# Main.net
KiCad netlist of a schematic drawn in Altium Designer
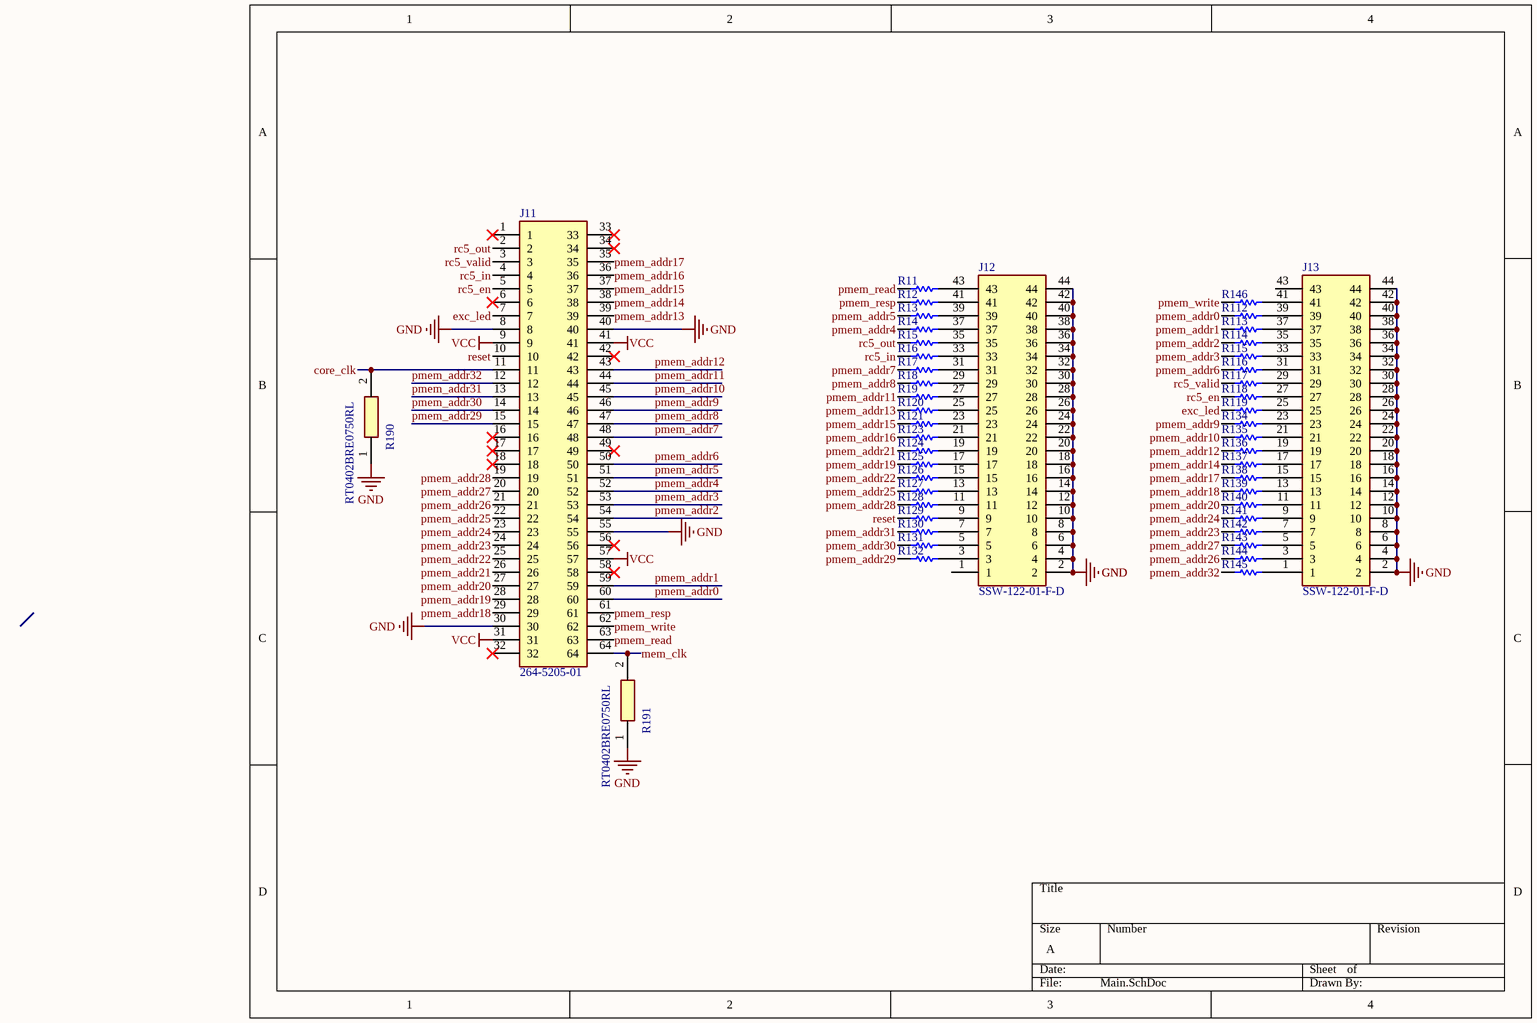
[diagram p0: Main.SchDoc]

(export (version "E")
  (design (tool "Eeschema 10.0.6"))
  (components
    (comp (ref "J11")
      (value "264-5205-01")
      (footprint "SamacSys:264-5205-01_1")
      (description "Connector")
      (fields (field (name "MOUSER PART NUMBER") "517-264-5205-01"))
      (libsource (lib "*") (part "264-5205-01"))
    )
    (comp (ref "J12")
      (value "SSW-122-01-F-D")
      (footprint "SamacSys:SSW-122-XX-YYY-D")
      (description "Connector")
      (fields (field (name "MOUSER PART NUMBER") "200-SSW12201FD"))
      (libsource (lib "SamacSys") (part "SSW-122-01-F-D"))
    )
    (comp (ref "J13")
      (value "SSW-122-01-F-D")
      (footprint "SamacSys:SSW-122-XX-YYY-D")
      (description "Connector")
      (fields (field (name "MOUSER PART NUMBER") "200-SSW12201FD"))
      (libsource (lib "SamacSys") (part "SSW-122-01-F-D"))
    )
    (comp (ref "R11")
      (value "ERJ-U020R00X")
      (footprint "RESC1005X40X25NL05T10")
      (fields (field (name "MANUFACTURER") "Panasonic"))
      (libsource (lib "Altium Content Vault") (part "RES"))
    )
    (comp (ref "R12")
      (value "ERJ-U020R00X")
      (footprint "RESC1005X40X25NL05T10")
      (fields (field (name "MANUFACTURER") "Panasonic"))
      (libsource (lib "Altium Content Vault") (part "RES"))
    )
    (comp (ref "R13")
      (value "ERJ-U020R00X")
      (footprint "RESC1005X40X25NL05T10")
      (fields (field (name "MANUFACTURER") "Panasonic"))
      (libsource (lib "Altium Content Vault") (part "RES"))
    )
    (comp (ref "R14")
      (value "ERJ-U020R00X")
      (footprint "RESC1005X40X25NL05T10")
      (fields (field (name "MANUFACTURER") "Panasonic"))
      (libsource (lib "Altium Content Vault") (part "RES"))
    )
    (comp (ref "R15")
      (value "ERJ-U020R00X")
      (footprint "RESC1005X40X25NL05T10")
      (fields (field (name "MANUFACTURER") "Panasonic"))
      (libsource (lib "Altium Content Vault") (part "RES"))
    )
    (comp (ref "R16")
      (value "ERJ-U020R00X")
      (footprint "RESC1005X40X25NL05T10")
      (fields (field (name "MANUFACTURER") "Panasonic"))
      (libsource (lib "Altium Content Vault") (part "RES"))
    )
    (comp (ref "R17")
      (value "ERJ-U020R00X")
      (footprint "RESC1005X40X25NL05T10")
      (fields (field (name "MANUFACTURER") "Panasonic"))
      (libsource (lib "Altium Content Vault") (part "RES"))
    )
    (comp (ref "R18")
      (value "ERJ-U020R00X")
      (footprint "RESC1005X40X25NL05T10")
      (fields (field (name "MANUFACTURER") "Panasonic"))
      (libsource (lib "Altium Content Vault") (part "RES"))
    )
    (comp (ref "R19")
      (value "ERJ-U020R00X")
      (footprint "RESC1005X40X25NL05T10")
      (fields (field (name "MANUFACTURER") "Panasonic"))
      (libsource (lib "Altium Content Vault") (part "RES"))
    )
    (comp (ref "R112")
      (value "ERJ-U020R00X")
      (footprint "RESC1005X40X25NL05T10")
      (fields (field (name "MANUFACTURER") "Panasonic"))
      (libsource (lib "Altium Content Vault") (part "RES"))
    )
    (comp (ref "R113")
      (value "ERJ-U020R00X")
      (footprint "RESC1005X40X25NL05T10")
      (fields (field (name "MANUFACTURER") "Panasonic"))
      (libsource (lib "Altium Content Vault") (part "RES"))
    )
    (comp (ref "R114")
      (value "ERJ-U020R00X")
      (footprint "RESC1005X40X25NL05T10")
      (fields (field (name "MANUFACTURER") "Panasonic"))
      (libsource (lib "Altium Content Vault") (part "RES"))
    )
    (comp (ref "R115")
      (value "ERJ-U020R00X")
      (footprint "RESC1005X40X25NL05T10")
      (fields (field (name "MANUFACTURER") "Panasonic"))
      (libsource (lib "Altium Content Vault") (part "RES"))
    )
    (comp (ref "R116")
      (value "ERJ-U020R00X")
      (footprint "RESC1005X40X25NL05T10")
      (fields (field (name "MANUFACTURER") "Panasonic"))
      (libsource (lib "Altium Content Vault") (part "RES"))
    )
    (comp (ref "R117")
      (value "ERJ-U020R00X")
      (footprint "RESC1005X40X25NL05T10")
      (fields (field (name "MANUFACTURER") "Panasonic"))
      (libsource (lib "Altium Content Vault") (part "RES"))
    )
    (comp (ref "R118")
      (value "ERJ-U020R00X")
      (footprint "RESC1005X40X25NL05T10")
      (fields (field (name "MANUFACTURER") "Panasonic"))
      (libsource (lib "Altium Content Vault") (part "RES"))
    )
    (comp (ref "R119")
      (value "ERJ-U020R00X")
      (footprint "RESC1005X40X25NL05T10")
      (fields (field (name "MANUFACTURER") "Panasonic"))
      (libsource (lib "Altium Content Vault") (part "RES"))
    )
    (comp (ref "R120")
      (value "ERJ-U020R00X")
      (footprint "RESC1005X40X25NL05T10")
      (fields (field (name "MANUFACTURER") "Panasonic"))
      (libsource (lib "Altium Content Vault") (part "RES"))
    )
    (comp (ref "R121")
      (value "ERJ-U020R00X")
      (footprint "RESC1005X40X25NL05T10")
      (fields (field (name "MANUFACTURER") "Panasonic"))
      (libsource (lib "Altium Content Vault") (part "RES"))
    )
    (comp (ref "R123")
      (value "ERJ-U020R00X")
      (footprint "RESC1005X40X25NL05T10")
      (fields (field (name "MANUFACTURER") "Panasonic"))
      (libsource (lib "Altium Content Vault") (part "RES"))
    )
    (comp (ref "R124")
      (value "ERJ-U020R00X")
      (footprint "RESC1005X40X25NL05T10")
      (fields (field (name "MANUFACTURER") "Panasonic"))
      (libsource (lib "Altium Content Vault") (part "RES"))
    )
    (comp (ref "R125")
      (value "ERJ-U020R00X")
      (footprint "RESC1005X40X25NL05T10")
      (fields (field (name "MANUFACTURER") "Panasonic"))
      (libsource (lib "Altium Content Vault") (part "RES"))
    )
    (comp (ref "R126")
      (value "ERJ-U020R00X")
      (footprint "RESC1005X40X25NL05T10")
      (fields (field (name "MANUFACTURER") "Panasonic"))
      (libsource (lib "Altium Content Vault") (part "RES"))
    )
    (comp (ref "R127")
      (value "ERJ-U020R00X")
      (footprint "RESC1005X40X25NL05T10")
      (fields (field (name "MANUFACTURER") "Panasonic"))
      (libsource (lib "Altium Content Vault") (part "RES"))
    )
    (comp (ref "R128")
      (value "ERJ-U020R00X")
      (footprint "RESC1005X40X25NL05T10")
      (fields (field (name "MANUFACTURER") "Panasonic"))
      (libsource (lib "Altium Content Vault") (part "RES"))
    )
    (comp (ref "R129")
      (value "ERJ-U020R00X")
      (footprint "RESC1005X40X25NL05T10")
      (fields (field (name "MANUFACTURER") "Panasonic"))
      (libsource (lib "Altium Content Vault") (part "RES"))
    )
    (comp (ref "R130")
      (value "ERJ-U020R00X")
      (footprint "RESC1005X40X25NL05T10")
      (fields (field (name "MANUFACTURER") "Panasonic"))
      (libsource (lib "Altium Content Vault") (part "RES"))
    )
    (comp (ref "R131")
      (value "ERJ-U020R00X")
      (footprint "RESC1005X40X25NL05T10")
      (fields (field (name "MANUFACTURER") "Panasonic"))
      (libsource (lib "Altium Content Vault") (part "RES"))
    )
    (comp (ref "R132")
      (value "ERJ-U020R00X")
      (footprint "RESC1005X40X25NL05T10")
      (fields (field (name "MANUFACTURER") "Panasonic"))
      (libsource (lib "Altium Content Vault") (part "RES"))
    )
    (comp (ref "R134")
      (value "ERJ-U020R00X")
      (footprint "RESC1005X40X25NL05T10")
      (fields (field (name "MANUFACTURER") "Panasonic"))
      (libsource (lib "Altium Content Vault") (part "RES"))
    )
    (comp (ref "R135")
      (value "ERJ-U020R00X")
      (footprint "RESC1005X40X25NL05T10")
      (fields (field (name "MANUFACTURER") "Panasonic"))
      (libsource (lib "Altium Content Vault") (part "RES"))
    )
    (comp (ref "R136")
      (value "ERJ-U020R00X")
      (footprint "RESC1005X40X25NL05T10")
      (fields (field (name "MANUFACTURER") "Panasonic"))
      (libsource (lib "Altium Content Vault") (part "RES"))
    )
    (comp (ref "R137")
      (value "ERJ-U020R00X")
      (footprint "RESC1005X40X25NL05T10")
      (fields (field (name "MANUFACTURER") "Panasonic"))
      (libsource (lib "Altium Content Vault") (part "RES"))
    )
    (comp (ref "R138")
      (value "ERJ-U020R00X")
      (footprint "RESC1005X40X25NL05T10")
      (fields (field (name "MANUFACTURER") "Panasonic"))
      (libsource (lib "Altium Content Vault") (part "RES"))
    )
    (comp (ref "R139")
      (value "ERJ-U020R00X")
      (footprint "RESC1005X40X25NL05T10")
      (fields (field (name "MANUFACTURER") "Panasonic"))
      (libsource (lib "Altium Content Vault") (part "RES"))
    )
    (comp (ref "R140")
      (value "ERJ-U020R00X")
      (footprint "RESC1005X40X25NL05T10")
      (fields (field (name "MANUFACTURER") "Panasonic"))
      (libsource (lib "Altium Content Vault") (part "RES"))
    )
    (comp (ref "R141")
      (value "ERJ-U020R00X")
      (footprint "RESC1005X40X25NL05T10")
      (fields (field (name "MANUFACTURER") "Panasonic"))
      (libsource (lib "Altium Content Vault") (part "RES"))
    )
    (comp (ref "R142")
      (value "ERJ-U020R00X")
      (footprint "RESC1005X40X25NL05T10")
      (fields (field (name "MANUFACTURER") "Panasonic"))
      (libsource (lib "Altium Content Vault") (part "RES"))
    )
    (comp (ref "R143")
      (value "ERJ-U020R00X")
      (footprint "RESC1005X40X25NL05T10")
      (fields (field (name "MANUFACTURER") "Panasonic"))
      (libsource (lib "Altium Content Vault") (part "RES"))
    )
    (comp (ref "R144")
      (value "ERJ-U020R00X")
      (footprint "RESC1005X40X25NL05T10")
      (fields (field (name "MANUFACTURER") "Panasonic"))
      (libsource (lib "Altium Content Vault") (part "RES"))
    )
    (comp (ref "R145")
      (value "ERJ-U020R00X")
      (footprint "RESC1005X40X25NL05T10")
      (fields (field (name "MANUFACTURER") "Panasonic"))
      (libsource (lib "Altium Content Vault") (part "RES"))
    )
    (comp (ref "R146")
      (value "ERJ-U020R00X")
      (footprint "RESC1005X40X25NL05T10")
      (fields (field (name "MANUFACTURER") "Panasonic"))
      (libsource (lib "Altium Content Vault") (part "RES"))
    )
    (comp (ref "R190")
      (value "RT0402BRE0750RL")
      (footprint "SamacSys:RESC1005X35N")
      (description "Resistor")
      (fields (field (name "MOUSER PART NUMBER") "603-RT0402BRE0750RL"))
      (libsource (lib "*") (part "RT0402BRE0750RL"))
    )
    (comp (ref "R191")
      (value "RT0402BRE0750RL")
      (footprint "SamacSys:RESC1005X35N")
      (description "Resistor")
      (fields (field (name "MOUSER PART NUMBER") "603-RT0402BRE0750RL"))
      (libsource (lib "*") (part "RT0402BRE0750RL"))
    )
  )
  (nets
    (net (code "1") (name "/core_clk") (class "Default")
      (node (ref "J11") (pin "11") (pinfunction "11_11") (pintype "passive"))
      (node (ref "R190") (pin "2") (pinfunction "2_2") (pintype "passive"))
    )
    (net (code "2") (name "/exc_led") (class "Default")
      (node (ref "J11") (pin "7") (pinfunction "7_7") (pintype "passive"))
      (node (ref "R119") (pin "1") (pinfunction "1_1") (pintype "passive"))
    )
    (net (code "3") (name "/mem_clk") (class "Default")
      (node (ref "J11") (pin "64") (pinfunction "64_64") (pintype "passive"))
      (node (ref "R191") (pin "2") (pinfunction "2_2") (pintype "passive"))
    )
    (net (code "4") (name "/pmem_addr0") (class "Default")
      (node (ref "J11") (pin "60") (pinfunction "60_60") (pintype "passive"))
      (node (ref "R112") (pin "1") (pinfunction "1_1") (pintype "passive"))
    )
    (net (code "5") (name "/pmem_addr1") (class "Default")
      (node (ref "J11") (pin "59") (pinfunction "59_59") (pintype "passive"))
      (node (ref "R113") (pin "1") (pinfunction "1_1") (pintype "passive"))
    )
    (net (code "6") (name "/pmem_addr2") (class "Default")
      (node (ref "J11") (pin "54") (pinfunction "54_54") (pintype "passive"))
      (node (ref "R114") (pin "1") (pinfunction "1_1") (pintype "passive"))
    )
    (net (code "7") (name "/pmem_addr3") (class "Default")
      (node (ref "J11") (pin "53") (pinfunction "53_53") (pintype "passive"))
      (node (ref "R115") (pin "1") (pinfunction "1_1") (pintype "passive"))
    )
    (net (code "8") (name "/pmem_addr4") (class "Default")
      (node (ref "J11") (pin "52") (pinfunction "52_52") (pintype "passive"))
      (node (ref "R14") (pin "1") (pinfunction "1_1") (pintype "passive"))
    )
    (net (code "9") (name "/pmem_addr5") (class "Default")
      (node (ref "J11") (pin "51") (pinfunction "51_51") (pintype "passive"))
      (node (ref "R13") (pin "1") (pinfunction "1_1") (pintype "passive"))
    )
    (net (code "10") (name "/pmem_addr6") (class "Default")
      (node (ref "J11") (pin "50") (pinfunction "50_50") (pintype "passive"))
      (node (ref "R116") (pin "1") (pinfunction "1_1") (pintype "passive"))
    )
    (net (code "11") (name "/pmem_addr7") (class "Default")
      (node (ref "J11") (pin "48") (pinfunction "48_48") (pintype "passive"))
      (node (ref "R17") (pin "1") (pinfunction "1_1") (pintype "passive"))
    )
    (net (code "12") (name "/pmem_addr8") (class "Default")
      (node (ref "J11") (pin "47") (pinfunction "47_47") (pintype "passive"))
      (node (ref "R18") (pin "1") (pinfunction "1_1") (pintype "passive"))
    )
    (net (code "13") (name "/pmem_addr9") (class "Default")
      (node (ref "J11") (pin "46") (pinfunction "46_46") (pintype "passive"))
      (node (ref "R134") (pin "1") (pinfunction "1_1") (pintype "passive"))
    )
    (net (code "14") (name "/pmem_addr10") (class "Default")
      (node (ref "J11") (pin "45") (pinfunction "45_45") (pintype "passive"))
      (node (ref "R135") (pin "1") (pinfunction "1_1") (pintype "passive"))
    )
    (net (code "15") (name "/pmem_addr11") (class "Default")
      (node (ref "J11") (pin "44") (pinfunction "44_44") (pintype "passive"))
      (node (ref "R19") (pin "1") (pinfunction "1_1") (pintype "passive"))
    )
    (net (code "16") (name "/pmem_addr12") (class "Default")
      (node (ref "J11") (pin "43") (pinfunction "43_43") (pintype "passive"))
      (node (ref "R136") (pin "1") (pinfunction "1_1") (pintype "passive"))
    )
    (net (code "17") (name "/pmem_addr13") (class "Default")
      (node (ref "J11") (pin "39") (pinfunction "39_39") (pintype "passive"))
      (node (ref "R120") (pin "1") (pinfunction "1_1") (pintype "passive"))
    )
    (net (code "18") (name "/pmem_addr14") (class "Default")
      (node (ref "J11") (pin "38") (pinfunction "38_38") (pintype "passive"))
      (node (ref "R137") (pin "1") (pinfunction "1_1") (pintype "passive"))
    )
    (net (code "19") (name "/pmem_addr15") (class "Default")
      (node (ref "J11") (pin "37") (pinfunction "37_37") (pintype "passive"))
      (node (ref "R121") (pin "1") (pinfunction "1_1") (pintype "passive"))
    )
    (net (code "20") (name "/pmem_addr16") (class "Default")
      (node (ref "J11") (pin "36") (pinfunction "36_36") (pintype "passive"))
      (node (ref "R123") (pin "1") (pinfunction "1_1") (pintype "passive"))
    )
    (net (code "21") (name "/pmem_addr17") (class "Default")
      (node (ref "J11") (pin "35") (pinfunction "35_35") (pintype "passive"))
      (node (ref "R138") (pin "1") (pinfunction "1_1") (pintype "passive"))
    )
    (net (code "22") (name "/pmem_addr18") (class "Default")
      (node (ref "J11") (pin "29") (pinfunction "29_29") (pintype "passive"))
      (node (ref "R139") (pin "1") (pinfunction "1_1") (pintype "passive"))
    )
    (net (code "23") (name "/pmem_addr19") (class "Default")
      (node (ref "J11") (pin "28") (pinfunction "28_28") (pintype "passive"))
      (node (ref "R125") (pin "1") (pinfunction "1_1") (pintype "passive"))
    )
    (net (code "24") (name "/pmem_addr20") (class "Default")
      (node (ref "J11") (pin "27") (pinfunction "27_27") (pintype "passive"))
      (node (ref "R140") (pin "1") (pinfunction "1_1") (pintype "passive"))
    )
    (net (code "25") (name "/pmem_addr21") (class "Default")
      (node (ref "J11") (pin "26") (pinfunction "26_26") (pintype "passive"))
      (node (ref "R124") (pin "1") (pinfunction "1_1") (pintype "passive"))
    )
    (net (code "26") (name "/pmem_addr22") (class "Default")
      (node (ref "J11") (pin "25") (pinfunction "25_25") (pintype "passive"))
      (node (ref "R126") (pin "1") (pinfunction "1_1") (pintype "passive"))
    )
    (net (code "27") (name "/pmem_addr23") (class "Default")
      (node (ref "J11") (pin "24") (pinfunction "24_24") (pintype "passive"))
      (node (ref "R142") (pin "1") (pinfunction "1_1") (pintype "passive"))
    )
    (net (code "28") (name "/pmem_addr24") (class "Default")
      (node (ref "J11") (pin "23") (pinfunction "23_23") (pintype "passive"))
      (node (ref "R141") (pin "1") (pinfunction "1_1") (pintype "passive"))
    )
    (net (code "29") (name "/pmem_addr25") (class "Default")
      (node (ref "J11") (pin "22") (pinfunction "22_22") (pintype "passive"))
      (node (ref "R127") (pin "1") (pinfunction "1_1") (pintype "passive"))
    )
    (net (code "30") (name "/pmem_addr26") (class "Default")
      (node (ref "J11") (pin "21") (pinfunction "21_21") (pintype "passive"))
      (node (ref "R144") (pin "1") (pinfunction "1_1") (pintype "passive"))
    )
    (net (code "31") (name "/pmem_addr27") (class "Default")
      (node (ref "J11") (pin "20") (pinfunction "20_20") (pintype "passive"))
      (node (ref "R143") (pin "1") (pinfunction "1_1") (pintype "passive"))
    )
    (net (code "32") (name "/pmem_addr28") (class "Default")
      (node (ref "J11") (pin "19") (pinfunction "19_19") (pintype "passive"))
      (node (ref "R128") (pin "1") (pinfunction "1_1") (pintype "passive"))
    )
    (net (code "33") (name "/pmem_addr29") (class "Default")
      (node (ref "J11") (pin "15") (pinfunction "15_15") (pintype "passive"))
      (node (ref "R132") (pin "1") (pinfunction "1_1") (pintype "passive"))
    )
    (net (code "34") (name "/pmem_addr30") (class "Default")
      (node (ref "J11") (pin "14") (pinfunction "14_14") (pintype "passive"))
      (node (ref "R131") (pin "1") (pinfunction "1_1") (pintype "passive"))
    )
    (net (code "35") (name "/pmem_addr31") (class "Default")
      (node (ref "J11") (pin "13") (pinfunction "13_13") (pintype "passive"))
      (node (ref "R130") (pin "1") (pinfunction "1_1") (pintype "passive"))
    )
    (net (code "36") (name "/pmem_addr32") (class "Default")
      (node (ref "J11") (pin "12") (pinfunction "12_12") (pintype "passive"))
      (node (ref "R145") (pin "1") (pinfunction "1_1") (pintype "passive"))
    )
    (net (code "37") (name "/pmem_read") (class "Default")
      (node (ref "J11") (pin "63") (pinfunction "63_63") (pintype "passive"))
      (node (ref "R11") (pin "1") (pinfunction "1_1") (pintype "passive"))
    )
    (net (code "38") (name "/pmem_resp") (class "Default")
      (node (ref "J11") (pin "61") (pinfunction "61_61") (pintype "passive"))
      (node (ref "R12") (pin "1") (pinfunction "1_1") (pintype "passive"))
    )
    (net (code "39") (name "/pmem_write") (class "Default")
      (node (ref "J11") (pin "62") (pinfunction "62_62") (pintype "passive"))
      (node (ref "R146") (pin "1") (pinfunction "1_1") (pintype "passive"))
    )
    (net (code "40") (name "/rc5_en") (class "Default")
      (node (ref "J11") (pin "5") (pinfunction "5_5") (pintype "passive"))
      (node (ref "R118") (pin "1") (pinfunction "1_1") (pintype "passive"))
    )
    (net (code "41") (name "/rc5_in") (class "Default")
      (node (ref "J11") (pin "4") (pinfunction "4_4") (pintype "passive"))
      (node (ref "R16") (pin "1") (pinfunction "1_1") (pintype "passive"))
    )
    (net (code "42") (name "/rc5_out") (class "Default")
      (node (ref "J11") (pin "2") (pinfunction "2_2") (pintype "passive"))
      (node (ref "R15") (pin "1") (pinfunction "1_1") (pintype "passive"))
    )
    (net (code "43") (name "/rc5_valid") (class "Default")
      (node (ref "J11") (pin "3") (pinfunction "3_3") (pintype "passive"))
      (node (ref "R117") (pin "1") (pinfunction "1_1") (pintype "passive"))
    )
    (net (code "44") (name "/reset") (class "Default")
      (node (ref "J11") (pin "10") (pinfunction "10_10") (pintype "passive"))
      (node (ref "R129") (pin "1") (pinfunction "1_1") (pintype "passive"))
    )
    (net (code "45") (name "GND") (class "Default")
      (node (ref "J11") (pin "30") (pinfunction "30_30") (pintype "passive"))
      (node (ref "J11") (pin "40") (pinfunction "40_40") (pintype "passive"))
      (node (ref "J11") (pin "55") (pinfunction "55_55") (pintype "passive"))
      (node (ref "J11") (pin "8") (pinfunction "8_8") (pintype "passive"))
      (node (ref "J12") (pin "10") (pinfunction "10_10") (pintype "passive"))
      (node (ref "J12") (pin "12") (pinfunction "12_12") (pintype "passive"))
      (node (ref "J12") (pin "14") (pinfunction "14_14") (pintype "passive"))
      (node (ref "J12") (pin "16") (pinfunction "16_16") (pintype "passive"))
      (node (ref "J12") (pin "18") (pinfunction "18_18") (pintype "passive"))
      (node (ref "J12") (pin "2") (pinfunction "2_2") (pintype "passive"))
      (node (ref "J12") (pin "20") (pinfunction "20_20") (pintype "passive"))
      (node (ref "J12") (pin "22") (pinfunction "22_22") (pintype "passive"))
      (node (ref "J12") (pin "24") (pinfunction "24_24") (pintype "passive"))
      (node (ref "J12") (pin "26") (pinfunction "26_26") (pintype "passive"))
      (node (ref "J12") (pin "28") (pinfunction "28_28") (pintype "passive"))
      (node (ref "J12") (pin "30") (pinfunction "30_30") (pintype "passive"))
      (node (ref "J12") (pin "32") (pinfunction "32_32") (pintype "passive"))
      (node (ref "J12") (pin "34") (pinfunction "34_34") (pintype "passive"))
      (node (ref "J12") (pin "36") (pinfunction "36_36") (pintype "passive"))
      (node (ref "J12") (pin "38") (pinfunction "38_38") (pintype "passive"))
      (node (ref "J12") (pin "4") (pinfunction "4_4") (pintype "passive"))
      (node (ref "J12") (pin "40") (pinfunction "40_40") (pintype "passive"))
      (node (ref "J12") (pin "42") (pinfunction "42_42") (pintype "passive"))
      (node (ref "J12") (pin "44") (pinfunction "44_44") (pintype "passive"))
      (node (ref "J12") (pin "6") (pinfunction "6_6") (pintype "passive"))
      (node (ref "J12") (pin "8") (pinfunction "8_8") (pintype "passive"))
      (node (ref "J13") (pin "10") (pinfunction "10_10") (pintype "passive"))
      (node (ref "J13") (pin "12") (pinfunction "12_12") (pintype "passive"))
      (node (ref "J13") (pin "14") (pinfunction "14_14") (pintype "passive"))
      (node (ref "J13") (pin "16") (pinfunction "16_16") (pintype "passive"))
      (node (ref "J13") (pin "18") (pinfunction "18_18") (pintype "passive"))
      (node (ref "J13") (pin "2") (pinfunction "2_2") (pintype "passive"))
      (node (ref "J13") (pin "20") (pinfunction "20_20") (pintype "passive"))
      (node (ref "J13") (pin "22") (pinfunction "22_22") (pintype "passive"))
      (node (ref "J13") (pin "24") (pinfunction "24_24") (pintype "passive"))
      (node (ref "J13") (pin "26") (pinfunction "26_26") (pintype "passive"))
      (node (ref "J13") (pin "28") (pinfunction "28_28") (pintype "passive"))
      (node (ref "J13") (pin "30") (pinfunction "30_30") (pintype "passive"))
      (node (ref "J13") (pin "32") (pinfunction "32_32") (pintype "passive"))
      (node (ref "J13") (pin "34") (pinfunction "34_34") (pintype "passive"))
      (node (ref "J13") (pin "36") (pinfunction "36_36") (pintype "passive"))
      (node (ref "J13") (pin "38") (pinfunction "38_38") (pintype "passive"))
      (node (ref "J13") (pin "4") (pinfunction "4_4") (pintype "passive"))
      (node (ref "J13") (pin "40") (pinfunction "40_40") (pintype "passive"))
      (node (ref "J13") (pin "42") (pinfunction "42_42") (pintype "passive"))
      (node (ref "J13") (pin "44") (pinfunction "44_44") (pintype "passive"))
      (node (ref "J13") (pin "6") (pinfunction "6_6") (pintype "passive"))
      (node (ref "J13") (pin "8") (pinfunction "8_8") (pintype "passive"))
      (node (ref "R190") (pin "1") (pinfunction "1_1") (pintype "passive"))
      (node (ref "R191") (pin "1") (pinfunction "1_1") (pintype "passive"))
    )
    (net (code "46") (name "Net-(J12-Pad3)") (class "Default")
      (node (ref "J12") (pin "3") (pinfunction "3_3") (pintype "passive"))
      (node (ref "R132") (pin "2") (pinfunction "2_2") (pintype "passive"))
    )
    (net (code "47") (name "Net-(J12-Pad5)") (class "Default")
      (node (ref "J12") (pin "5") (pinfunction "5_5") (pintype "passive"))
      (node (ref "R131") (pin "2") (pinfunction "2_2") (pintype "passive"))
    )
    (net (code "48") (name "Net-(J12-Pad7)") (class "Default")
      (node (ref "J12") (pin "7") (pinfunction "7_7") (pintype "passive"))
      (node (ref "R130") (pin "2") (pinfunction "2_2") (pintype "passive"))
    )
    (net (code "49") (name "Net-(J12-Pad9)") (class "Default")
      (node (ref "J12") (pin "9") (pinfunction "9_9") (pintype "passive"))
      (node (ref "R129") (pin "2") (pinfunction "2_2") (pintype "passive"))
    )
    (net (code "50") (name "Net-(J12-Pad11)") (class "Default")
      (node (ref "J12") (pin "11") (pinfunction "11_11") (pintype "passive"))
      (node (ref "R128") (pin "2") (pinfunction "2_2") (pintype "passive"))
    )
    (net (code "51") (name "Net-(J12-Pad13)") (class "Default")
      (node (ref "J12") (pin "13") (pinfunction "13_13") (pintype "passive"))
      (node (ref "R127") (pin "2") (pinfunction "2_2") (pintype "passive"))
    )
    (net (code "52") (name "Net-(J12-Pad15)") (class "Default")
      (node (ref "J12") (pin "15") (pinfunction "15_15") (pintype "passive"))
      (node (ref "R126") (pin "2") (pinfunction "2_2") (pintype "passive"))
    )
    (net (code "53") (name "Net-(J12-Pad17)") (class "Default")
      (node (ref "J12") (pin "17") (pinfunction "17_17") (pintype "passive"))
      (node (ref "R125") (pin "2") (pinfunction "2_2") (pintype "passive"))
    )
    (net (code "54") (name "Net-(J12-Pad19)") (class "Default")
      (node (ref "J12") (pin "19") (pinfunction "19_19") (pintype "passive"))
      (node (ref "R124") (pin "2") (pinfunction "2_2") (pintype "passive"))
    )
    (net (code "55") (name "Net-(J12-Pad21)") (class "Default")
      (node (ref "J12") (pin "21") (pinfunction "21_21") (pintype "passive"))
      (node (ref "R123") (pin "2") (pinfunction "2_2") (pintype "passive"))
    )
    (net (code "56") (name "Net-(J12-Pad23)") (class "Default")
      (node (ref "J12") (pin "23") (pinfunction "23_23") (pintype "passive"))
      (node (ref "R121") (pin "2") (pinfunction "2_2") (pintype "passive"))
    )
    (net (code "57") (name "Net-(J12-Pad25)") (class "Default")
      (node (ref "J12") (pin "25") (pinfunction "25_25") (pintype "passive"))
      (node (ref "R120") (pin "2") (pinfunction "2_2") (pintype "passive"))
    )
    (net (code "58") (name "Net-(J12-Pad27)") (class "Default")
      (node (ref "J12") (pin "27") (pinfunction "27_27") (pintype "passive"))
      (node (ref "R19") (pin "2") (pinfunction "2_2") (pintype "passive"))
    )
    (net (code "59") (name "Net-(J12-Pad29)") (class "Default")
      (node (ref "J12") (pin "29") (pinfunction "29_29") (pintype "passive"))
      (node (ref "R18") (pin "2") (pinfunction "2_2") (pintype "passive"))
    )
    (net (code "60") (name "Net-(J12-Pad31)") (class "Default")
      (node (ref "J12") (pin "31") (pinfunction "31_31") (pintype "passive"))
      (node (ref "R17") (pin "2") (pinfunction "2_2") (pintype "passive"))
    )
    (net (code "61") (name "Net-(J12-Pad33)") (class "Default")
      (node (ref "J12") (pin "33") (pinfunction "33_33") (pintype "passive"))
      (node (ref "R16") (pin "2") (pinfunction "2_2") (pintype "passive"))
    )
    (net (code "62") (name "Net-(J12-Pad35)") (class "Default")
      (node (ref "J12") (pin "35") (pinfunction "35_35") (pintype "passive"))
      (node (ref "R15") (pin "2") (pinfunction "2_2") (pintype "passive"))
    )
    (net (code "63") (name "Net-(J12-Pad37)") (class "Default")
      (node (ref "J12") (pin "37") (pinfunction "37_37") (pintype "passive"))
      (node (ref "R14") (pin "2") (pinfunction "2_2") (pintype "passive"))
    )
    (net (code "64") (name "Net-(J12-Pad39)") (class "Default")
      (node (ref "J12") (pin "39") (pinfunction "39_39") (pintype "passive"))
      (node (ref "R13") (pin "2") (pinfunction "2_2") (pintype "passive"))
    )
    (net (code "65") (name "Net-(J12-Pad41)") (class "Default")
      (node (ref "J12") (pin "41") (pinfunction "41_41") (pintype "passive"))
      (node (ref "R12") (pin "2") (pinfunction "2_2") (pintype "passive"))
    )
    (net (code "66") (name "Net-(J12-Pad43)") (class "Default")
      (node (ref "J12") (pin "43") (pinfunction "43_43") (pintype "passive"))
      (node (ref "R11") (pin "2") (pinfunction "2_2") (pintype "passive"))
    )
    (net (code "67") (name "Net-(J13-Pad1)") (class "Default")
      (node (ref "J13") (pin "1") (pinfunction "1_1") (pintype "passive"))
      (node (ref "R145") (pin "2") (pinfunction "2_2") (pintype "passive"))
    )
    (net (code "68") (name "Net-(J13-Pad3)") (class "Default")
      (node (ref "J13") (pin "3") (pinfunction "3_3") (pintype "passive"))
      (node (ref "R144") (pin "2") (pinfunction "2_2") (pintype "passive"))
    )
    (net (code "69") (name "Net-(J13-Pad5)") (class "Default")
      (node (ref "J13") (pin "5") (pinfunction "5_5") (pintype "passive"))
      (node (ref "R143") (pin "2") (pinfunction "2_2") (pintype "passive"))
    )
    (net (code "70") (name "Net-(J13-Pad7)") (class "Default")
      (node (ref "J13") (pin "7") (pinfunction "7_7") (pintype "passive"))
      (node (ref "R142") (pin "2") (pinfunction "2_2") (pintype "passive"))
    )
    (net (code "71") (name "Net-(J13-Pad9)") (class "Default")
      (node (ref "J13") (pin "9") (pinfunction "9_9") (pintype "passive"))
      (node (ref "R141") (pin "2") (pinfunction "2_2") (pintype "passive"))
    )
    (net (code "72") (name "Net-(J13-Pad11)") (class "Default")
      (node (ref "J13") (pin "11") (pinfunction "11_11") (pintype "passive"))
      (node (ref "R140") (pin "2") (pinfunction "2_2") (pintype "passive"))
    )
    (net (code "73") (name "Net-(J13-Pad13)") (class "Default")
      (node (ref "J13") (pin "13") (pinfunction "13_13") (pintype "passive"))
      (node (ref "R139") (pin "2") (pinfunction "2_2") (pintype "passive"))
    )
    (net (code "74") (name "Net-(J13-Pad15)") (class "Default")
      (node (ref "J13") (pin "15") (pinfunction "15_15") (pintype "passive"))
      (node (ref "R138") (pin "2") (pinfunction "2_2") (pintype "passive"))
    )
    (net (code "75") (name "Net-(J13-Pad17)") (class "Default")
      (node (ref "J13") (pin "17") (pinfunction "17_17") (pintype "passive"))
      (node (ref "R137") (pin "2") (pinfunction "2_2") (pintype "passive"))
    )
    (net (code "76") (name "Net-(J13-Pad19)") (class "Default")
      (node (ref "J13") (pin "19") (pinfunction "19_19") (pintype "passive"))
      (node (ref "R136") (pin "2") (pinfunction "2_2") (pintype "passive"))
    )
    (net (code "77") (name "Net-(J13-Pad21)") (class "Default")
      (node (ref "J13") (pin "21") (pinfunction "21_21") (pintype "passive"))
      (node (ref "R135") (pin "2") (pinfunction "2_2") (pintype "passive"))
    )
    (net (code "78") (name "Net-(J13-Pad23)") (class "Default")
      (node (ref "J13") (pin "23") (pinfunction "23_23") (pintype "passive"))
      (node (ref "R134") (pin "2") (pinfunction "2_2") (pintype "passive"))
    )
    (net (code "79") (name "Net-(J13-Pad25)") (class "Default")
      (node (ref "J13") (pin "25") (pinfunction "25_25") (pintype "passive"))
      (node (ref "R119") (pin "2") (pinfunction "2_2") (pintype "passive"))
    )
    (net (code "80") (name "Net-(J13-Pad27)") (class "Default")
      (node (ref "J13") (pin "27") (pinfunction "27_27") (pintype "passive"))
      (node (ref "R118") (pin "2") (pinfunction "2_2") (pintype "passive"))
    )
    (net (code "81") (name "Net-(J13-Pad29)") (class "Default")
      (node (ref "J13") (pin "29") (pinfunction "29_29") (pintype "passive"))
      (node (ref "R117") (pin "2") (pinfunction "2_2") (pintype "passive"))
    )
    (net (code "82") (name "Net-(J13-Pad31)") (class "Default")
      (node (ref "J13") (pin "31") (pinfunction "31_31") (pintype "passive"))
      (node (ref "R116") (pin "2") (pinfunction "2_2") (pintype "passive"))
    )
    (net (code "83") (name "Net-(J13-Pad33)") (class "Default")
      (node (ref "J13") (pin "33") (pinfunction "33_33") (pintype "passive"))
      (node (ref "R115") (pin "2") (pinfunction "2_2") (pintype "passive"))
    )
    (net (code "84") (name "Net-(J13-Pad35)") (class "Default")
      (node (ref "J13") (pin "35") (pinfunction "35_35") (pintype "passive"))
      (node (ref "R114") (pin "2") (pinfunction "2_2") (pintype "passive"))
    )
    (net (code "85") (name "Net-(J13-Pad37)") (class "Default")
      (node (ref "J13") (pin "37") (pinfunction "37_37") (pintype "passive"))
      (node (ref "R113") (pin "2") (pinfunction "2_2") (pintype "passive"))
    )
    (net (code "86") (name "Net-(J13-Pad39)") (class "Default")
      (node (ref "J13") (pin "39") (pinfunction "39_39") (pintype "passive"))
      (node (ref "R112") (pin "2") (pinfunction "2_2") (pintype "passive"))
    )
    (net (code "87") (name "Net-(J13-Pad41)") (class "Default")
      (node (ref "J13") (pin "41") (pinfunction "41_41") (pintype "passive"))
      (node (ref "R146") (pin "2") (pinfunction "2_2") (pintype "passive"))
    )
    (net (code "88") (name "VCC") (class "Default")
      (node (ref "J11") (pin "31") (pinfunction "31_31") (pintype "passive"))
      (node (ref "J11") (pin "41") (pinfunction "41_41") (pintype "passive"))
      (node (ref "J11") (pin "57") (pinfunction "57_57") (pintype "passive"))
      (node (ref "J11") (pin "9") (pinfunction "9_9") (pintype "passive"))
    )
    (net (code "89") (name "unconnected-(J11-Pad1)") (class "Default")
      (node (ref "J11") (pin "1") (pinfunction "1_1") (pintype "passive+no_connect"))
    )
    (net (code "90") (name "unconnected-(J11-Pad6)") (class "Default")
      (node (ref "J11") (pin "6") (pinfunction "6_6") (pintype "passive+no_connect"))
    )
    (net (code "91") (name "unconnected-(J11-Pad16)") (class "Default")
      (node (ref "J11") (pin "16") (pinfunction "16_16") (pintype "passive+no_connect"))
    )
    (net (code "92") (name "unconnected-(J11-Pad17)") (class "Default")
      (node (ref "J11") (pin "17") (pinfunction "17_17") (pintype "passive+no_connect"))
    )
    (net (code "93") (name "unconnected-(J11-Pad18)") (class "Default")
      (node (ref "J11") (pin "18") (pinfunction "18_18") (pintype "passive+no_connect"))
    )
    (net (code "94") (name "unconnected-(J11-Pad32)") (class "Default")
      (node (ref "J11") (pin "32") (pinfunction "32_32") (pintype "passive+no_connect"))
    )
    (net (code "95") (name "unconnected-(J11-Pad33)") (class "Default")
      (node (ref "J11") (pin "33") (pinfunction "33_33") (pintype "passive+no_connect"))
    )
    (net (code "96") (name "unconnected-(J11-Pad34)") (class "Default")
      (node (ref "J11") (pin "34") (pinfunction "34_34") (pintype "passive+no_connect"))
    )
    (net (code "97") (name "unconnected-(J11-Pad42)") (class "Default")
      (node (ref "J11") (pin "42") (pinfunction "42_42") (pintype "passive+no_connect"))
    )
    (net (code "98") (name "unconnected-(J11-Pad49)") (class "Default")
      (node (ref "J11") (pin "49") (pinfunction "49_49") (pintype "passive+no_connect"))
    )
    (net (code "99") (name "unconnected-(J11-Pad56)") (class "Default")
      (node (ref "J11") (pin "56") (pinfunction "56_56") (pintype "passive+no_connect"))
    )
    (net (code "100") (name "unconnected-(J11-Pad58)") (class "Default")
      (node (ref "J11") (pin "58") (pinfunction "58_58") (pintype "passive+no_connect"))
    )
    (net (code "101") (name "unconnected-(J12-Pad1)") (class "Default")
      (node (ref "J12") (pin "1") (pinfunction "1_1") (pintype "passive"))
    )
    (net (code "102") (name "unconnected-(J13-Pad43)") (class "Default")
      (node (ref "J13") (pin "43") (pinfunction "43_43") (pintype "passive"))
    )
  )
)
